# design.net
KiCad netlist of a schematic drawn in Altium Designer
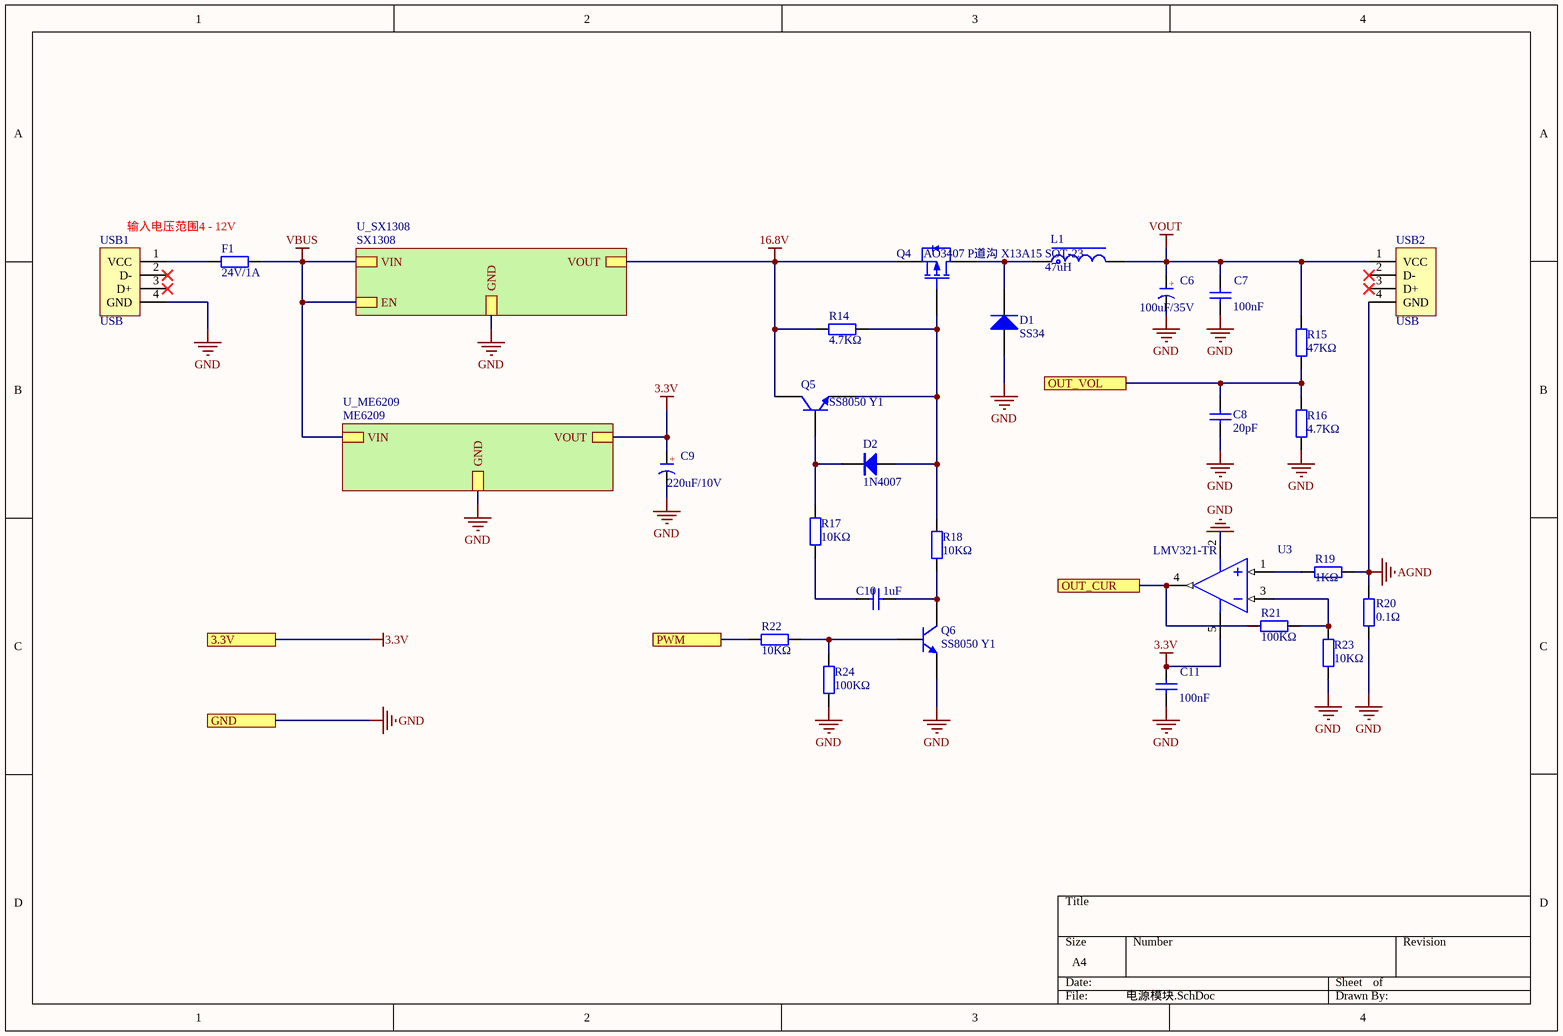
[diagram p0: 电源模块.SchDoc]

(export (version "E")
  (design (tool "Eeschema 10.0.6"))
  (components
    (comp (ref "C6")
      (value "100uF/35V")
      (footprint "CAP 2.5*6.3*11.2-H")
      (description "直插电解电容")
      (libsource (lib "0.1 - 电阻-电容-电感") (part "CE"))
    )
    (comp (ref "C7")
      (value "100nF")
      (footprint "LC-0603_C")
      (description "贴片电容")
      (libsource (lib "Miscellaneous Devices LC") (part "0603 100nF (104) 10% 50V"))
    )
    (comp (ref "C8")
      (value "20pF")
      (footprint "LC-0603_C")
      (description "贴片电容")
      (libsource (lib "Miscellaneous Devices LC") (part "0603 20pF (200) 5% 50V"))
    )
    (comp (ref "C9")
      (value "220uF/10V")
      (footprint "CAP 2.0*5*11-H")
      (description "直插电解电容")
      (libsource (lib "0.1 - 电阻-电容-电感") (part "CE"))
    )
    (comp (ref "C10")
      (value "1uF")
      (footprint "LC-0603_C")
      (description "贴片电容")
      (libsource (lib "Miscellaneous Devices LC") (part "0603 1uF (105) 10% 50V"))
    )
    (comp (ref "C11")
      (value "100nF")
      (footprint "LC-0603_C")
      (description "贴片电容")
      (libsource (lib "Miscellaneous Devices LC") (part "0603 100nF (104) 10% 50V"))
    )
    (comp (ref "D1")
      (value "SS34")
      (footprint "LC-SMA(DO-214AC)_S1")
      (description "二极管")
      (libsource (lib "Miscellaneous Devices LC") (part "SMA(DO-214AC) SS54"))
    )
    (comp (ref "D2")
      (value "1N4007")
      (footprint "SOD-323")
      (description "开关二极管")
      (libsource (lib "0.2 -  二极管-整流桥") (part "1N4148"))
    )
    (comp (ref "F1")
      (value "24V/1A")
      (footprint "1206")
      (description "自恢复保险丝")
      (fields (field (name "Comment") "MF-NSMF020-2 0.2A 24V") (field (name "PUBLISHER") "Altium Limited"))
      (libsource (lib "user_Library") (part "MF-NSMF020-2 0.2A 24V"))
    )
    (comp (ref "L1")
      (value "47uH")
      (footprint "CDRH73")
      (description "功率屏蔽电感")
      (fields (field (name "版权归属") "封装库来自淘宝 ID：黄晶宝石"))
      (libsource (lib "0.1 - 电阻-电容-电感") (part "L-CDRH"))
    )
    (comp (ref "Q4")
      (value "AO3407 P道沟 X13A15 SOT-23")
      (footprint "LC-SOT-23(SOT-23-3)")
      (description "MOS(场效应管)")
      (libsource (lib "Miscellaneous Devices LC") (part "AO3401A P道沟 X13A15 SOT-23"))
    )
    (comp (ref "Q5")
      (value "SS8050 Y1")
      (footprint "LC-SOT-23(SOT-23-3)")
      (description "三极管")
      (libsource (lib "Miscellaneous Devices LC") (part "SOT-23 SS8050 Y1"))
    )
    (comp (ref "Q6")
      (value "SS8050 Y1")
      (footprint "LC-SOT-23(SOT-23-3)")
      (description "三极管")
      (libsource (lib "Miscellaneous Devices LC") (part "SOT-23 SS8050 Y1"))
    )
    (comp (ref "R14")
      (value "4.7KΩ")
      (footprint "LC-0603_R")
      (description "贴片电阻")
      (libsource (lib "Miscellaneous Devices LC") (part "0603 4.7KΩ (4701) 1%"))
    )
    (comp (ref "R15")
      (value "47KΩ")
      (footprint "LC-0603_R")
      (description "贴片电阻")
      (libsource (lib "") (part "0603 100KΩ (1003) 1%_1"))
    )
    (comp (ref "R16")
      (value "4.7KΩ")
      (footprint "LC-0603_R")
      (description "贴片电阻")
      (libsource (lib "") (part "0603 10KΩ (1002) 1%_2"))
    )
    (comp (ref "R17")
      (value "10KΩ")
      (footprint "LC-0603_R")
      (description "贴片电阻")
      (libsource (lib "") (part "0603 10KΩ (1002) 1%_2"))
    )
    (comp (ref "R18")
      (value "10KΩ")
      (footprint "LC-0603_R")
      (description "贴片电阻")
      (libsource (lib "") (part "0603 10KΩ (1002) 1%_2"))
    )
    (comp (ref "R19")
      (value "1KΩ")
      (footprint "LC-0603_R")
      (description "贴片电阻")
      (libsource (lib "Miscellaneous Devices LC") (part "0603 1KΩ (1001) 1%"))
    )
    (comp (ref "R20")
      (value "0.1Ω")
      (footprint "R 2512_L")
      (description "贴片电阻")
      (fields (field (name "版权归属") "来自淘宝 ID：黄晶宝石"))
      (libsource (lib "0.1 - 电阻-电容-电感") (part "R"))
    )
    (comp (ref "R21")
      (value "100KΩ")
      (footprint "LC-0603_R")
      (description "贴片电阻")
      (libsource (lib "") (part "0603 100KΩ (1003) 1%_2"))
    )
    (comp (ref "R22")
      (value "10KΩ")
      (footprint "LC-0603_R")
      (description "贴片电阻")
      (libsource (lib "Miscellaneous Devices LC") (part "0603 10KΩ (1002) 1%"))
    )
    (comp (ref "R23")
      (value "10KΩ")
      (footprint "LC-0603_R")
      (description "贴片电阻")
      (libsource (lib "") (part "0603 10KΩ (1002) 1%_1"))
    )
    (comp (ref "R24")
      (value "100KΩ")
      (footprint "LC-0603_R")
      (description "贴片电阻")
      (libsource (lib "Miscellaneous Devices LC") (part "0603 100KΩ (1003) 1%"))
    )
    (comp (ref "U3")
      (value "LMV321-TR")
      (footprint "LC-SOT-23-5")
      (description "运放")
      (libsource (lib "Miscellaneous Devices LC") (part "LMV321IDBVRG4"))
    )
    (comp (ref "USB1")
      (value "USB")
      (footprint "USB_A/P_A")
      (description "USB-A型公接口")
      (fields (field (name "版权归属") "封装库来自淘宝卖家 ID：黄晶宝石"))
      (libsource (lib "0.8 - 以太网-音频-USB插座") (part "USB-A/P"))
    )
    (comp (ref "USB2")
      (value "USB")
      (footprint "USB-A/S_A")
      (description "USB-A型母接口")
      (fields (field (name "版权归属") "封装库来自淘宝 ID：黄晶宝石"))
      (libsource (lib "0.8 - 以太网-音频-USB插座") (part "USB-A/S"))
    )
  )
  (nets
    (net (code "1") (name "/OUT_CUR") (class "Default")
      (node (ref "R21") (pin "2") (pinfunction "2_2") (pintype "passive"))
      (node (ref "U3") (pin "4") (pinfunction "OUT_4") (pintype "output"))
    )
    (net (code "2") (name "/OUT_VOL") (class "Default")
      (node (ref "C8") (pin "2") (pinfunction "2_2") (pintype "passive"))
      (node (ref "R15") (pin "1") (pinfunction "1_1") (pintype "passive"))
      (node (ref "R16") (pin "2") (pinfunction "2_2") (pintype "passive"))
    )
    (net (code "3") (name "/PWM") (class "Default")
      (node (ref "R22") (pin "2") (pinfunction "2_2") (pintype "passive"))
    )
    (net (code "4") (name "3.3V") (class "Default")
      (node (ref "C11") (pin "2") (pinfunction "2_2") (pintype "passive"))
      (node (ref "C9") (pin "1") (pinfunction "A_1") (pintype "passive"))
      (node (ref "U3") (pin "5") (pinfunction "V+_5") (pintype "power_in"))
    )
    (net (code "5") (name "16.8V") (class "Default")
      (node (ref "Q4") (pin "2") (pinfunction "S_2") (pintype "passive"))
      (node (ref "Q5") (pin "3") (pinfunction "C_3") (pintype "passive"))
      (node (ref "R14") (pin "2") (pinfunction "2_2") (pintype "passive"))
    )
    (net (code "6") (name "AGND") (class "Default")
      (node (ref "R19") (pin "1") (pinfunction "1_1") (pintype "passive"))
      (node (ref "R20") (pin "2") (pinfunction "2_2") (pintype "passive"))
      (node (ref "USB2") (pin "4") (pinfunction "GND_4") (pintype "passive"))
    )
    (net (code "7") (name "GND") (class "Default")
      (node (ref "C11") (pin "1") (pinfunction "1_1") (pintype "passive"))
      (node (ref "C6") (pin "2") (pinfunction "K_2") (pintype "passive"))
      (node (ref "C7") (pin "1") (pinfunction "1_1") (pintype "passive"))
      (node (ref "C8") (pin "1") (pinfunction "1_1") (pintype "passive"))
      (node (ref "C9") (pin "2") (pinfunction "K_2") (pintype "passive"))
      (node (ref "D1") (pin "1") (pinfunction "A_1") (pintype "passive"))
      (node (ref "Q6") (pin "2") (pinfunction "E_2") (pintype "passive"))
      (node (ref "R16") (pin "1") (pinfunction "1_1") (pintype "passive"))
      (node (ref "R20") (pin "1") (pinfunction "1_1") (pintype "passive"))
      (node (ref "R23") (pin "2") (pinfunction "2_2") (pintype "passive"))
      (node (ref "R24") (pin "2") (pinfunction "2_2") (pintype "passive"))
      (node (ref "U3") (pin "2") (pinfunction "V-_2") (pintype "power_in"))
      (node (ref "USB1") (pin "4") (pinfunction "GND_4") (pintype "passive"))
    )
    (net (code "8") (name "Net-(C10-Pad1)") (class "Default")
      (node (ref "C10") (pin "1") (pinfunction "1_1") (pintype "passive"))
      (node (ref "R17") (pin "1") (pinfunction "1_1") (pintype "passive"))
    )
    (net (code "9") (name "Net-(D1-K)") (class "Default")
      (node (ref "D1") (pin "2") (pinfunction "K_2") (pintype "passive"))
      (node (ref "L1") (pin "1") (pinfunction "1_1") (pintype "passive"))
      (node (ref "Q4") (pin "3") (pinfunction "D_3") (pintype "passive"))
    )
    (net (code "10") (name "Net-(D2-A)") (class "Default")
      (node (ref "D2") (pin "1") (pinfunction "A_1") (pintype "passive"))
      (node (ref "Q4") (pin "1") (pinfunction "G_1") (pintype "passive"))
      (node (ref "Q5") (pin "2") (pinfunction "E_2") (pintype "passive"))
      (node (ref "R14") (pin "1") (pinfunction "1_1") (pintype "passive"))
      (node (ref "R18") (pin "2") (pinfunction "2_2") (pintype "passive"))
    )
    (net (code "11") (name "Net-(D2-K)") (class "Default")
      (node (ref "D2") (pin "2") (pinfunction "K_2") (pintype "passive"))
      (node (ref "Q5") (pin "1") (pinfunction "B_1") (pintype "passive"))
      (node (ref "R17") (pin "2") (pinfunction "2_2") (pintype "passive"))
    )
    (net (code "12") (name "Net-(Q6-B)") (class "Default")
      (node (ref "Q6") (pin "1") (pinfunction "B_1") (pintype "passive"))
      (node (ref "R22") (pin "1") (pinfunction "1_1") (pintype "passive"))
      (node (ref "R24") (pin "1") (pinfunction "1_1") (pintype "passive"))
    )
    (net (code "13") (name "Net-(Q6-C)") (class "Default")
      (node (ref "C10") (pin "2") (pinfunction "2_2") (pintype "passive"))
      (node (ref "Q6") (pin "3") (pinfunction "C_3") (pintype "passive"))
      (node (ref "R18") (pin "1") (pinfunction "1_1") (pintype "passive"))
    )
    (net (code "14") (name "Net-(U3-IN+)") (class "Default")
      (node (ref "R19") (pin "2") (pinfunction "2_2") (pintype "passive"))
      (node (ref "U3") (pin "1") (pinfunction "IN+_1") (pintype "input"))
    )
    (net (code "15") (name "Net-(U3-IN-)") (class "Default")
      (node (ref "R21") (pin "1") (pinfunction "1_1") (pintype "passive"))
      (node (ref "R23") (pin "1") (pinfunction "1_1") (pintype "passive"))
      (node (ref "U3") (pin "3") (pinfunction "IN-_3") (pintype "input"))
    )
    (net (code "16") (name "Net-(USB1-VCC)") (class "Default")
      (node (ref "F1") (pin "1") (pinfunction "1_1") (pintype "passive"))
      (node (ref "USB1") (pin "1") (pinfunction "VCC_1") (pintype "passive"))
    )
    (net (code "17") (name "VBUS") (class "Default")
      (node (ref "F1") (pin "2") (pinfunction "2_2") (pintype "passive"))
    )
    (net (code "18") (name "VOUT") (class "Default")
      (node (ref "C6") (pin "1") (pinfunction "A_1") (pintype "passive"))
      (node (ref "C7") (pin "2") (pinfunction "2_2") (pintype "passive"))
      (node (ref "L1") (pin "2") (pinfunction "2_2") (pintype "passive"))
      (node (ref "R15") (pin "2") (pinfunction "2_2") (pintype "passive"))
      (node (ref "USB2") (pin "1") (pinfunction "VCC_1") (pintype "passive"))
    )
    (net (code "19") (name "unconnected-(USB1-D+-Pad3)") (class "Default")
      (node (ref "USB1") (pin "3") (pinfunction "D+_3") (pintype "passive+no_connect"))
    )
    (net (code "20") (name "unconnected-(USB1-D--Pad2)") (class "Default")
      (node (ref "USB1") (pin "2") (pinfunction "D-_2") (pintype "passive+no_connect"))
    )
    (net (code "21") (name "unconnected-(USB2-D+-Pad3)") (class "Default")
      (node (ref "USB2") (pin "3") (pinfunction "D+_3") (pintype "passive+no_connect"))
    )
    (net (code "22") (name "unconnected-(USB2-D--Pad2)") (class "Default")
      (node (ref "USB2") (pin "2") (pinfunction "D-_2") (pintype "passive+no_connect"))
    )
  )
)
